# Relevadores.net
KiCad netlist of a schematic drawn in EAGLE
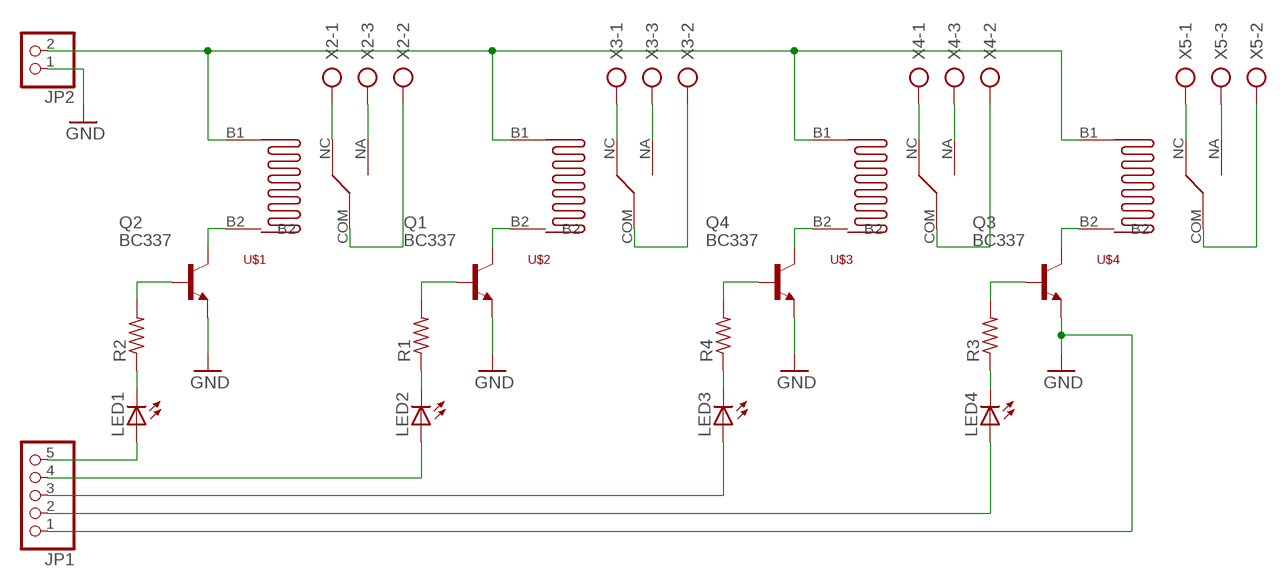
[diagram p0: schematic, sheet 1]

(export (version "E")
  (design (tool "Eeschema 10.0.6"))
  (components
    (comp (ref "JP1")
      (value "PINHD-1X5/90")
      (footprint "eagle-import:1X05_90")
      (libsource (lib "eagle-import") (part "PINHD-1X5/90"))
    )
    (comp (ref "JP2")
      (value "PINHD-1X2/90")
      (footprint "eagle-import:1X02_90")
      (libsource (lib "eagle-import") (part "PINHD-1X2/90"))
    )
    (comp (ref "LED1")
      (value "LED3MM")
      (footprint "eagle-import:LED3MM")
      (libsource (lib "eagle-import") (part "LED3MM"))
    )
    (comp (ref "LED2")
      (value "LED3MM")
      (footprint "eagle-import:LED3MM")
      (libsource (lib "eagle-import") (part "LED3MM"))
    )
    (comp (ref "LED3")
      (value "LED3MM")
      (footprint "eagle-import:LED3MM")
      (libsource (lib "eagle-import") (part "LED3MM"))
    )
    (comp (ref "LED4")
      (value "LED3MM")
      (footprint "eagle-import:LED3MM")
      (libsource (lib "eagle-import") (part "LED3MM"))
    )
    (comp (ref "Q1")
      (value "BC337")
      (footprint "eagle-import:TO92")
      (libsource (lib "eagle-import") (part "BC337"))
    )
    (comp (ref "Q2")
      (value "BC337")
      (footprint "eagle-import:TO92")
      (libsource (lib "eagle-import") (part "BC337"))
    )
    (comp (ref "Q3")
      (value "BC337")
      (footprint "eagle-import:TO92")
      (libsource (lib "eagle-import") (part "BC337"))
    )
    (comp (ref "Q4")
      (value "BC337")
      (footprint "eagle-import:TO92")
      (libsource (lib "eagle-import") (part "BC337"))
    )
    (comp (ref "R1")
      (value "R-US_0207/2V")
      (footprint "eagle-import:0207_2V")
      (libsource (lib "eagle-import") (part "R-US_0207/2V"))
    )
    (comp (ref "R2")
      (value "R-US_0207/2V")
      (footprint "eagle-import:0207_2V")
      (libsource (lib "eagle-import") (part "R-US_0207/2V"))
    )
    (comp (ref "R3")
      (value "R-US_0207/2V")
      (footprint "eagle-import:0207_2V")
      (libsource (lib "eagle-import") (part "R-US_0207/2V"))
    )
    (comp (ref "R4")
      (value "R-US_0207/2V")
      (footprint "eagle-import:0207_2V")
      (libsource (lib "eagle-import") (part "R-US_0207/2V"))
    )
    (comp (ref "U$1")
      (value "RAS-0510")
      (footprint "eagle-import:RAS-0510")
      (libsource (lib "eagle-import") (part "RAS-0510"))
    )
    (comp (ref "U$2")
      (value "RAS-0510")
      (footprint "eagle-import:RAS-0510")
      (libsource (lib "eagle-import") (part "RAS-0510"))
    )
    (comp (ref "U$3")
      (value "RAS-0510")
      (footprint "eagle-import:RAS-0510")
      (libsource (lib "eagle-import") (part "RAS-0510"))
    )
    (comp (ref "U$4")
      (value "RAS-0510")
      (footprint "eagle-import:RAS-0510")
      (libsource (lib "eagle-import") (part "RAS-0510"))
    )
    (comp (ref "X2")
      (value "AK300/3")
      (footprint "eagle-import:AK300_3")
      (libsource (lib "eagle-import") (part "AK300/3"))
    )
    (comp (ref "X3")
      (value "AK300/3")
      (footprint "eagle-import:AK300_3")
      (libsource (lib "eagle-import") (part "AK300/3"))
    )
    (comp (ref "X4")
      (value "AK300/3")
      (footprint "eagle-import:AK300_3")
      (libsource (lib "eagle-import") (part "AK300/3"))
    )
    (comp (ref "X5")
      (value "AK300/3")
      (footprint "eagle-import:AK300_3")
      (libsource (lib "eagle-import") (part "AK300/3"))
    )
  )
  (nets
    (net (code "1") (name "GND") (class "Default")
      (node (ref "JP1") (pin "1") (pinfunction "1_1") (pintype "passive"))
      (node (ref "JP2") (pin "1") (pinfunction "1_1") (pintype "passive"))
      (node (ref "Q1") (pin "1") (pinfunction "E_1") (pintype "passive"))
      (node (ref "Q2") (pin "1") (pinfunction "E_1") (pintype "passive"))
      (node (ref "Q3") (pin "1") (pinfunction "E_1") (pintype "passive"))
      (node (ref "Q4") (pin "1") (pinfunction "E_1") (pintype "passive"))
    )
    (net (code "2") (name "Net-(JP1-Pad2)") (class "Default")
      (node (ref "JP1") (pin "2") (pinfunction "2_2") (pintype "passive"))
      (node (ref "LED4") (pin "A") (pinfunction "A_A") (pintype "passive"))
    )
    (net (code "3") (name "Net-(JP1-Pad3)") (class "Default")
      (node (ref "JP1") (pin "3") (pinfunction "3_3") (pintype "passive"))
      (node (ref "LED3") (pin "A") (pinfunction "A_A") (pintype "passive"))
    )
    (net (code "4") (name "Net-(JP1-Pad4)") (class "Default")
      (node (ref "JP1") (pin "4") (pinfunction "4_4") (pintype "passive"))
      (node (ref "LED2") (pin "A") (pinfunction "A_A") (pintype "passive"))
    )
    (net (code "5") (name "Net-(JP1-Pad5)") (class "Default")
      (node (ref "JP1") (pin "5") (pinfunction "5_5") (pintype "passive"))
      (node (ref "LED1") (pin "A") (pinfunction "A_A") (pintype "passive"))
    )
    (net (code "6") (name "Net-(JP2-Pad2)") (class "Default")
      (node (ref "JP2") (pin "2") (pinfunction "2_2") (pintype "passive"))
      (node (ref "U$1") (pin "B1") (pinfunction "B1_B1") (pintype "bidirectional"))
      (node (ref "U$2") (pin "B1") (pinfunction "B1_B1") (pintype "bidirectional"))
      (node (ref "U$3") (pin "B1") (pinfunction "B1_B1") (pintype "bidirectional"))
      (node (ref "U$4") (pin "B1") (pinfunction "B1_B1") (pintype "bidirectional"))
    )
    (net (code "7") (name "Net-(LED1-C)") (class "Default")
      (node (ref "LED1") (pin "K") (pinfunction "C_K") (pintype "passive"))
      (node (ref "R2") (pin "1") (pinfunction "1_1") (pintype "passive"))
    )
    (net (code "8") (name "Net-(LED2-C)") (class "Default")
      (node (ref "LED2") (pin "K") (pinfunction "C_K") (pintype "passive"))
      (node (ref "R1") (pin "1") (pinfunction "1_1") (pintype "passive"))
    )
    (net (code "9") (name "Net-(LED3-C)") (class "Default")
      (node (ref "LED3") (pin "K") (pinfunction "C_K") (pintype "passive"))
      (node (ref "R4") (pin "1") (pinfunction "1_1") (pintype "passive"))
    )
    (net (code "10") (name "Net-(LED4-C)") (class "Default")
      (node (ref "LED4") (pin "K") (pinfunction "C_K") (pintype "passive"))
      (node (ref "R3") (pin "1") (pinfunction "1_1") (pintype "passive"))
    )
    (net (code "11") (name "Net-(Q1-B)") (class "Default")
      (node (ref "Q1") (pin "2") (pinfunction "B_2") (pintype "passive"))
      (node (ref "R1") (pin "2") (pinfunction "2_2") (pintype "passive"))
    )
    (net (code "12") (name "Net-(Q1-C)") (class "Default")
      (node (ref "Q1") (pin "3") (pinfunction "C_3") (pintype "passive"))
      (node (ref "U$2") (pin "B2") (pinfunction "B2_B2") (pintype "bidirectional"))
    )
    (net (code "13") (name "Net-(Q2-B)") (class "Default")
      (node (ref "Q2") (pin "2") (pinfunction "B_2") (pintype "passive"))
      (node (ref "R2") (pin "2") (pinfunction "2_2") (pintype "passive"))
    )
    (net (code "14") (name "Net-(Q2-C)") (class "Default")
      (node (ref "Q2") (pin "3") (pinfunction "C_3") (pintype "passive"))
      (node (ref "U$1") (pin "B2") (pinfunction "B2_B2") (pintype "bidirectional"))
    )
    (net (code "15") (name "Net-(Q3-B)") (class "Default")
      (node (ref "Q3") (pin "2") (pinfunction "B_2") (pintype "passive"))
      (node (ref "R3") (pin "2") (pinfunction "2_2") (pintype "passive"))
    )
    (net (code "16") (name "Net-(Q3-C)") (class "Default")
      (node (ref "Q3") (pin "3") (pinfunction "C_3") (pintype "passive"))
      (node (ref "U$4") (pin "B2") (pinfunction "B2_B2") (pintype "bidirectional"))
    )
    (net (code "17") (name "Net-(Q4-B)") (class "Default")
      (node (ref "Q4") (pin "2") (pinfunction "B_2") (pintype "passive"))
      (node (ref "R4") (pin "2") (pinfunction "2_2") (pintype "passive"))
    )
    (net (code "18") (name "Net-(Q4-C)") (class "Default")
      (node (ref "Q4") (pin "3") (pinfunction "C_3") (pintype "passive"))
      (node (ref "U$3") (pin "B2") (pinfunction "B2_B2") (pintype "bidirectional"))
    )
    (net (code "19") (name "Net-(X2A-KL)") (class "Default")
      (node (ref "U$1") (pin "NC") (pinfunction "NC_NC") (pintype "bidirectional"))
      (node (ref "X2") (pin "1") (pinfunction "KL_1") (pintype "passive"))
    )
    (net (code "20") (name "Net-(X2B-KL)") (class "Default")
      (node (ref "U$1") (pin "COM") (pinfunction "COM_COM") (pintype "bidirectional"))
      (node (ref "X2") (pin "2") (pinfunction "KL_2") (pintype "passive"))
    )
    (net (code "21") (name "Net-(X2C-KL)") (class "Default")
      (node (ref "U$1") (pin "NA") (pinfunction "NA_NA") (pintype "bidirectional"))
      (node (ref "X2") (pin "3") (pinfunction "KL_3") (pintype "passive"))
    )
    (net (code "22") (name "Net-(X3A-KL)") (class "Default")
      (node (ref "U$2") (pin "NC") (pinfunction "NC_NC") (pintype "bidirectional"))
      (node (ref "X3") (pin "1") (pinfunction "KL_1") (pintype "passive"))
    )
    (net (code "23") (name "Net-(X3B-KL)") (class "Default")
      (node (ref "U$2") (pin "COM") (pinfunction "COM_COM") (pintype "bidirectional"))
      (node (ref "X3") (pin "2") (pinfunction "KL_2") (pintype "passive"))
    )
    (net (code "24") (name "Net-(X3C-KL)") (class "Default")
      (node (ref "U$2") (pin "NA") (pinfunction "NA_NA") (pintype "bidirectional"))
      (node (ref "X3") (pin "3") (pinfunction "KL_3") (pintype "passive"))
    )
    (net (code "25") (name "Net-(X4A-KL)") (class "Default")
      (node (ref "U$3") (pin "NC") (pinfunction "NC_NC") (pintype "bidirectional"))
      (node (ref "X4") (pin "1") (pinfunction "KL_1") (pintype "passive"))
    )
    (net (code "26") (name "Net-(X4B-KL)") (class "Default")
      (node (ref "U$3") (pin "COM") (pinfunction "COM_COM") (pintype "bidirectional"))
      (node (ref "X4") (pin "2") (pinfunction "KL_2") (pintype "passive"))
    )
    (net (code "27") (name "Net-(X4C-KL)") (class "Default")
      (node (ref "U$3") (pin "NA") (pinfunction "NA_NA") (pintype "bidirectional"))
      (node (ref "X4") (pin "3") (pinfunction "KL_3") (pintype "passive"))
    )
    (net (code "28") (name "Net-(X5A-KL)") (class "Default")
      (node (ref "U$4") (pin "NC") (pinfunction "NC_NC") (pintype "bidirectional"))
      (node (ref "X5") (pin "1") (pinfunction "KL_1") (pintype "passive"))
    )
    (net (code "29") (name "Net-(X5B-KL)") (class "Default")
      (node (ref "U$4") (pin "COM") (pinfunction "COM_COM") (pintype "bidirectional"))
      (node (ref "X5") (pin "2") (pinfunction "KL_2") (pintype "passive"))
    )
    (net (code "30") (name "Net-(X5C-KL)") (class "Default")
      (node (ref "U$4") (pin "NA") (pinfunction "NA_NA") (pintype "bidirectional"))
      (node (ref "X5") (pin "3") (pinfunction "KL_3") (pintype "passive"))
    )
  )
)
